# kludge2.net
KiCad netlist of a schematic drawn in EAGLE
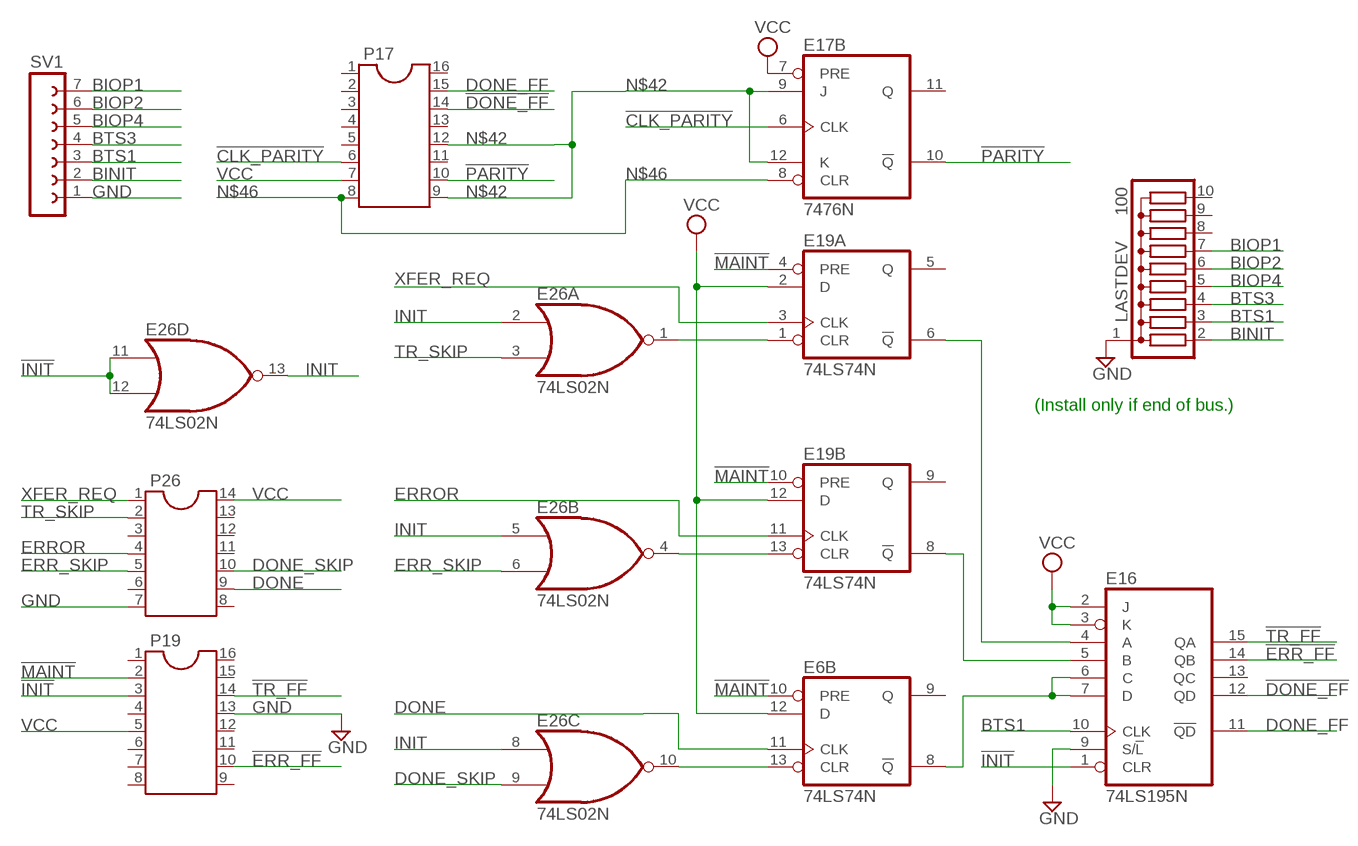
[diagram p0: schematic, sheet 1]

(export (version "E")
  (design (tool "Eeschema 10.0.6"))
  (components
    (comp (ref "E6")
      (value "74LS74N")
      (footprint "eagle-import:DIL14")
      (libsource (lib "eagle-import") (part "7474NLS"))
    )
    (comp (ref "E16")
      (value "74LS195N")
      (footprint "eagle-import:DIL16")
      (libsource (lib "eagle-import") (part "74195NLS"))
    )
    (comp (ref "E17")
      (value "7476N")
      (footprint "eagle-import:DIL16")
      (libsource (lib "eagle-import") (part "7476N"))
    )
    (comp (ref "E19")
      (value "74LS74N")
      (footprint "eagle-import:DIL14")
      (libsource (lib "eagle-import") (part "7474NLS"))
    )
    (comp (ref "E26")
      (value "74LS02N")
      (footprint "eagle-import:DIL14")
      (libsource (lib "eagle-import") (part "7402NLS"))
    )
    (comp (ref "LASTDEV")
      (value "100")
      (footprint "eagle-import:SIL10")
      (libsource (lib "eagle-import") (part "G09R"))
    )
    (comp (ref "P17")
      (value "DIL16")
      (footprint "eagle-import:DIL16")
      (libsource (lib "eagle-import") (part "DIL16"))
    )
    (comp (ref "P19")
      (value "DIL16")
      (footprint "eagle-import:DIL16")
      (libsource (lib "eagle-import") (part "DIL16"))
    )
    (comp (ref "P26")
      (value "DIL14")
      (footprint "eagle-import:DIL14")
      (libsource (lib "eagle-import") (part "DIL14"))
    )
    (comp (ref "SV1")
      (value "FE07-1")
      (footprint "eagle-import:FE07")
      (libsource (lib "eagle-import") (part "FE07-1"))
    )
  )
  (nets
    (net (code "1") (name "/BINIT") (class "Default")
      (node (ref "LASTDEV") (pin "2") (pinfunction "2_2") (pintype "passive"))
      (node (ref "SV1") (pin "2") (pinfunction "2_2") (pintype "passive"))
    )
    (net (code "2") (name "/BIOP1") (class "Default")
      (node (ref "LASTDEV") (pin "7") (pinfunction "7_7") (pintype "passive"))
      (node (ref "SV1") (pin "7") (pinfunction "7_7") (pintype "passive"))
    )
    (net (code "3") (name "/BIOP2") (class "Default")
      (node (ref "LASTDEV") (pin "6") (pinfunction "6_6") (pintype "passive"))
      (node (ref "SV1") (pin "6") (pinfunction "6_6") (pintype "passive"))
    )
    (net (code "4") (name "/BIOP4") (class "Default")
      (node (ref "LASTDEV") (pin "5") (pinfunction "5_5") (pintype "passive"))
      (node (ref "SV1") (pin "5") (pinfunction "5_5") (pintype "passive"))
    )
    (net (code "5") (name "/BTS1") (class "Default")
      (node (ref "E16") (pin "10") (pinfunction "CLK_10") (pintype "input"))
      (node (ref "LASTDEV") (pin "3") (pinfunction "3_3") (pintype "passive"))
      (node (ref "SV1") (pin "3") (pinfunction "3_3") (pintype "passive"))
    )
    (net (code "6") (name "/BTS3") (class "Default")
      (node (ref "LASTDEV") (pin "4") (pinfunction "4_4") (pintype "passive"))
      (node (ref "SV1") (pin "4") (pinfunction "4_4") (pintype "passive"))
    )
    (net (code "7") (name "/DONE") (class "Default")
      (node (ref "E6") (pin "11") (pinfunction "CLK_11") (pintype "input"))
      (node (ref "P26") (pin "9") (pinfunction "9_9") (pintype "passive"))
    )
    (net (code "8") (name "/DONE_FF") (class "Default")
      (node (ref "E16") (pin "11") (pinfunction "~{QD}_11") (pintype "output"))
      (node (ref "P17") (pin "15") (pinfunction "15_15") (pintype "passive"))
    )
    (net (code "9") (name "/DONE_SKIP") (class "Default")
      (node (ref "E26") (pin "9") (pinfunction "I1_9") (pintype "input"))
      (node (ref "P26") (pin "10") (pinfunction "10_10") (pintype "passive"))
    )
    (net (code "10") (name "/ERROR") (class "Default")
      (node (ref "E19") (pin "11") (pinfunction "CLK_11") (pintype "input"))
      (node (ref "P26") (pin "4") (pinfunction "4_4") (pintype "passive"))
    )
    (net (code "11") (name "/ERR_SKIP") (class "Default")
      (node (ref "E26") (pin "6") (pinfunction "I1_6") (pintype "input"))
      (node (ref "P26") (pin "5") (pinfunction "5_5") (pintype "passive"))
    )
    (net (code "12") (name "/INIT") (class "Default")
      (node (ref "E26") (pin "13") (pinfunction "O_13") (pintype "output"))
      (node (ref "E26") (pin "2") (pinfunction "I0_2") (pintype "input"))
      (node (ref "E26") (pin "5") (pinfunction "I0_5") (pintype "input"))
      (node (ref "E26") (pin "8") (pinfunction "I0_8") (pintype "input"))
    )
    (net (code "13") (name "/N$42") (class "Default")
      (node (ref "E17") (pin "12") (pinfunction "K_12") (pintype "input"))
      (node (ref "E17") (pin "9") (pinfunction "J_9") (pintype "input"))
      (node (ref "P17") (pin "12") (pinfunction "12_12") (pintype "passive"))
      (node (ref "P17") (pin "9") (pinfunction "9_9") (pintype "passive"))
    )
    (net (code "14") (name "/N$46") (class "Default")
      (node (ref "E17") (pin "8") (pinfunction "CLR_8") (pintype "input"))
      (node (ref "P17") (pin "8") (pinfunction "8_8") (pintype "passive"))
    )
    (net (code "15") (name "/TR_SKIP") (class "Default")
      (node (ref "E26") (pin "3") (pinfunction "I1_3") (pintype "input"))
      (node (ref "P26") (pin "2") (pinfunction "2_2") (pintype "passive"))
    )
    (net (code "16") (name "/XFER_REQ") (class "Default")
      (node (ref "E19") (pin "3") (pinfunction "CLK_3") (pintype "input"))
      (node (ref "P26") (pin "1") (pinfunction "1_1") (pintype "passive"))
    )
    (net (code "17") (name "/~{CLK_PARITY}") (class "Default")
      (node (ref "E17") (pin "6") (pinfunction "CLK_6") (pintype "input"))
      (node (ref "P17") (pin "6") (pinfunction "6_6") (pintype "passive"))
    )
    (net (code "18") (name "/~{DONE_FF}") (class "Default")
      (node (ref "E16") (pin "12") (pinfunction "QD_12") (pintype "output"))
      (node (ref "P17") (pin "14") (pinfunction "14_14") (pintype "passive"))
    )
    (net (code "19") (name "/~{ERR_FF}") (class "Default")
      (node (ref "E16") (pin "14") (pinfunction "QB_14") (pintype "output"))
      (node (ref "P19") (pin "10") (pinfunction "10_10") (pintype "passive"))
    )
    (net (code "20") (name "/~{INIT}") (class "Default")
      (node (ref "E16") (pin "1") (pinfunction "CLR_1") (pintype "input"))
      (node (ref "E26") (pin "11") (pinfunction "I0_11") (pintype "input"))
      (node (ref "E26") (pin "12") (pinfunction "I1_12") (pintype "input"))
      (node (ref "P19") (pin "3") (pinfunction "3_3") (pintype "passive"))
    )
    (net (code "21") (name "/~{MAINT}") (class "Default")
      (node (ref "E19") (pin "10") (pinfunction "PRE_10") (pintype "input"))
      (node (ref "E19") (pin "4") (pinfunction "PRE_4") (pintype "input"))
      (node (ref "E6") (pin "10") (pinfunction "PRE_10") (pintype "input"))
      (node (ref "P19") (pin "2") (pinfunction "2_2") (pintype "passive"))
    )
    (net (code "22") (name "/~{PARITY}") (class "Default")
      (node (ref "E17") (pin "10") (pinfunction "~{Q}_10") (pintype "output"))
      (node (ref "P17") (pin "10") (pinfunction "10_10") (pintype "passive"))
    )
    (net (code "23") (name "/~{TR_FF}") (class "Default")
      (node (ref "E16") (pin "15") (pinfunction "QA_15") (pintype "output"))
      (node (ref "P19") (pin "14") (pinfunction "14_14") (pintype "passive"))
    )
    (net (code "24") (name "GND") (class "Default")
      (node (ref "E16") (pin "9") (pinfunction "S/~{L}_9") (pintype "input"))
      (node (ref "LASTDEV") (pin "1") (pinfunction "1_1") (pintype "passive"))
      (node (ref "P19") (pin "13") (pinfunction "13_13") (pintype "passive"))
      (node (ref "P26") (pin "7") (pinfunction "7_7") (pintype "passive"))
      (node (ref "SV1") (pin "1") (pinfunction "1_1") (pintype "passive"))
    )
    (net (code "25") (name "Net-(E16A-A)") (class "Default")
      (node (ref "E16") (pin "4") (pinfunction "A_4") (pintype "input"))
      (node (ref "E19") (pin "6") (pinfunction "~{Q}_6") (pintype "output"))
    )
    (net (code "26") (name "Net-(E16A-B)") (class "Default")
      (node (ref "E16") (pin "5") (pinfunction "B_5") (pintype "input"))
      (node (ref "E19") (pin "8") (pinfunction "~{Q}_8") (pintype "output"))
    )
    (net (code "27") (name "Net-(E16A-C)") (class "Default")
      (node (ref "E16") (pin "6") (pinfunction "C_6") (pintype "input"))
      (node (ref "E16") (pin "7") (pinfunction "D_7") (pintype "input"))
      (node (ref "E6") (pin "8") (pinfunction "~{Q}_8") (pintype "output"))
    )
    (net (code "28") (name "Net-(E19A-CLR)") (class "Default")
      (node (ref "E19") (pin "1") (pinfunction "CLR_1") (pintype "input"))
      (node (ref "E26") (pin "1") (pinfunction "O_1") (pintype "output"))
    )
    (net (code "29") (name "Net-(E19B-CLR)") (class "Default")
      (node (ref "E19") (pin "13") (pinfunction "CLR_13") (pintype "input"))
      (node (ref "E26") (pin "4") (pinfunction "O_4") (pintype "output"))
    )
    (net (code "30") (name "Net-(E26C-O)") (class "Default")
      (node (ref "E26") (pin "10") (pinfunction "O_10") (pintype "output"))
      (node (ref "E6") (pin "13") (pinfunction "CLR_13") (pintype "input"))
    )
    (net (code "31") (name "VCC") (class "Default")
      (node (ref "E16") (pin "2") (pinfunction "J_2") (pintype "input"))
      (node (ref "E16") (pin "3") (pinfunction "K_3") (pintype "input"))
      (node (ref "E17") (pin "7") (pinfunction "PRE_7") (pintype "input"))
      (node (ref "E19") (pin "12") (pinfunction "D_12") (pintype "input"))
      (node (ref "E19") (pin "2") (pinfunction "D_2") (pintype "input"))
      (node (ref "E6") (pin "12") (pinfunction "D_12") (pintype "input"))
      (node (ref "P17") (pin "7") (pinfunction "7_7") (pintype "passive"))
      (node (ref "P19") (pin "5") (pinfunction "5_5") (pintype "passive"))
      (node (ref "P26") (pin "14") (pinfunction "14_14") (pintype "passive"))
    )
    (net (code "32") (name "unconnected-(E6B-Q-Pad9)") (class "Default")
      (node (ref "E6") (pin "9") (pinfunction "Q_9") (pintype "output"))
    )
    (net (code "33") (name "unconnected-(E16A-QC-Pad13)") (class "Default")
      (node (ref "E16") (pin "13") (pinfunction "QC_13") (pintype "output"))
    )
    (net (code "34") (name "unconnected-(E17B-Q-Pad11)") (class "Default")
      (node (ref "E17") (pin "11") (pinfunction "Q_11") (pintype "output"))
    )
    (net (code "35") (name "unconnected-(E19A-Q-Pad5)") (class "Default")
      (node (ref "E19") (pin "5") (pinfunction "Q_5") (pintype "output"))
    )
    (net (code "36") (name "unconnected-(E19B-Q-Pad9)") (class "Default")
      (node (ref "E19") (pin "9") (pinfunction "Q_9") (pintype "output"))
    )
    (net (code "37") (name "unconnected-(LASTDEV-Pad8)") (class "Default")
      (node (ref "LASTDEV") (pin "8") (pinfunction "8_8") (pintype "passive"))
    )
    (net (code "38") (name "unconnected-(LASTDEV-Pad9)") (class "Default")
      (node (ref "LASTDEV") (pin "9") (pinfunction "9_9") (pintype "passive"))
    )
    (net (code "39") (name "unconnected-(LASTDEV-Pad10)") (class "Default")
      (node (ref "LASTDEV") (pin "10") (pinfunction "10_10") (pintype "passive"))
    )
    (net (code "40") (name "unconnected-(P17-Pad1)") (class "Default")
      (node (ref "P17") (pin "1") (pinfunction "1_1") (pintype "passive"))
    )
    (net (code "41") (name "unconnected-(P17-Pad2)") (class "Default")
      (node (ref "P17") (pin "2") (pinfunction "2_2") (pintype "passive"))
    )
    (net (code "42") (name "unconnected-(P17-Pad3)") (class "Default")
      (node (ref "P17") (pin "3") (pinfunction "3_3") (pintype "passive"))
    )
    (net (code "43") (name "unconnected-(P17-Pad4)") (class "Default")
      (node (ref "P17") (pin "4") (pinfunction "4_4") (pintype "passive"))
    )
    (net (code "44") (name "unconnected-(P17-Pad5)") (class "Default")
      (node (ref "P17") (pin "5") (pinfunction "5_5") (pintype "passive"))
    )
    (net (code "45") (name "unconnected-(P17-Pad11)") (class "Default")
      (node (ref "P17") (pin "11") (pinfunction "11_11") (pintype "passive"))
    )
    (net (code "46") (name "unconnected-(P17-Pad13)") (class "Default")
      (node (ref "P17") (pin "13") (pinfunction "13_13") (pintype "passive"))
    )
    (net (code "47") (name "unconnected-(P17-Pad16)") (class "Default")
      (node (ref "P17") (pin "16") (pinfunction "16_16") (pintype "passive"))
    )
    (net (code "48") (name "unconnected-(P19-Pad1)") (class "Default")
      (node (ref "P19") (pin "1") (pinfunction "1_1") (pintype "passive"))
    )
    (net (code "49") (name "unconnected-(P19-Pad4)") (class "Default")
      (node (ref "P19") (pin "4") (pinfunction "4_4") (pintype "passive"))
    )
    (net (code "50") (name "unconnected-(P19-Pad6)") (class "Default")
      (node (ref "P19") (pin "6") (pinfunction "6_6") (pintype "passive"))
    )
    (net (code "51") (name "unconnected-(P19-Pad7)") (class "Default")
      (node (ref "P19") (pin "7") (pinfunction "7_7") (pintype "passive"))
    )
    (net (code "52") (name "unconnected-(P19-Pad8)") (class "Default")
      (node (ref "P19") (pin "8") (pinfunction "8_8") (pintype "passive"))
    )
    (net (code "53") (name "unconnected-(P19-Pad9)") (class "Default")
      (node (ref "P19") (pin "9") (pinfunction "9_9") (pintype "passive"))
    )
    (net (code "54") (name "unconnected-(P19-Pad11)") (class "Default")
      (node (ref "P19") (pin "11") (pinfunction "11_11") (pintype "passive"))
    )
    (net (code "55") (name "unconnected-(P19-Pad12)") (class "Default")
      (node (ref "P19") (pin "12") (pinfunction "12_12") (pintype "passive"))
    )
    (net (code "56") (name "unconnected-(P19-Pad15)") (class "Default")
      (node (ref "P19") (pin "15") (pinfunction "15_15") (pintype "passive"))
    )
    (net (code "57") (name "unconnected-(P19-Pad16)") (class "Default")
      (node (ref "P19") (pin "16") (pinfunction "16_16") (pintype "passive"))
    )
    (net (code "58") (name "unconnected-(P26-Pad3)") (class "Default")
      (node (ref "P26") (pin "3") (pinfunction "3_3") (pintype "passive"))
    )
    (net (code "59") (name "unconnected-(P26-Pad6)") (class "Default")
      (node (ref "P26") (pin "6") (pinfunction "6_6") (pintype "passive"))
    )
    (net (code "60") (name "unconnected-(P26-Pad8)") (class "Default")
      (node (ref "P26") (pin "8") (pinfunction "8_8") (pintype "passive"))
    )
    (net (code "61") (name "unconnected-(P26-Pad11)") (class "Default")
      (node (ref "P26") (pin "11") (pinfunction "11_11") (pintype "passive"))
    )
    (net (code "62") (name "unconnected-(P26-Pad12)") (class "Default")
      (node (ref "P26") (pin "12") (pinfunction "12_12") (pintype "passive"))
    )
    (net (code "63") (name "unconnected-(P26-Pad13)") (class "Default")
      (node (ref "P26") (pin "13") (pinfunction "13_13") (pintype "passive"))
    )
  )
)
